# RH055_1.net
KiCad netlist of a schematic drawn in EAGLE
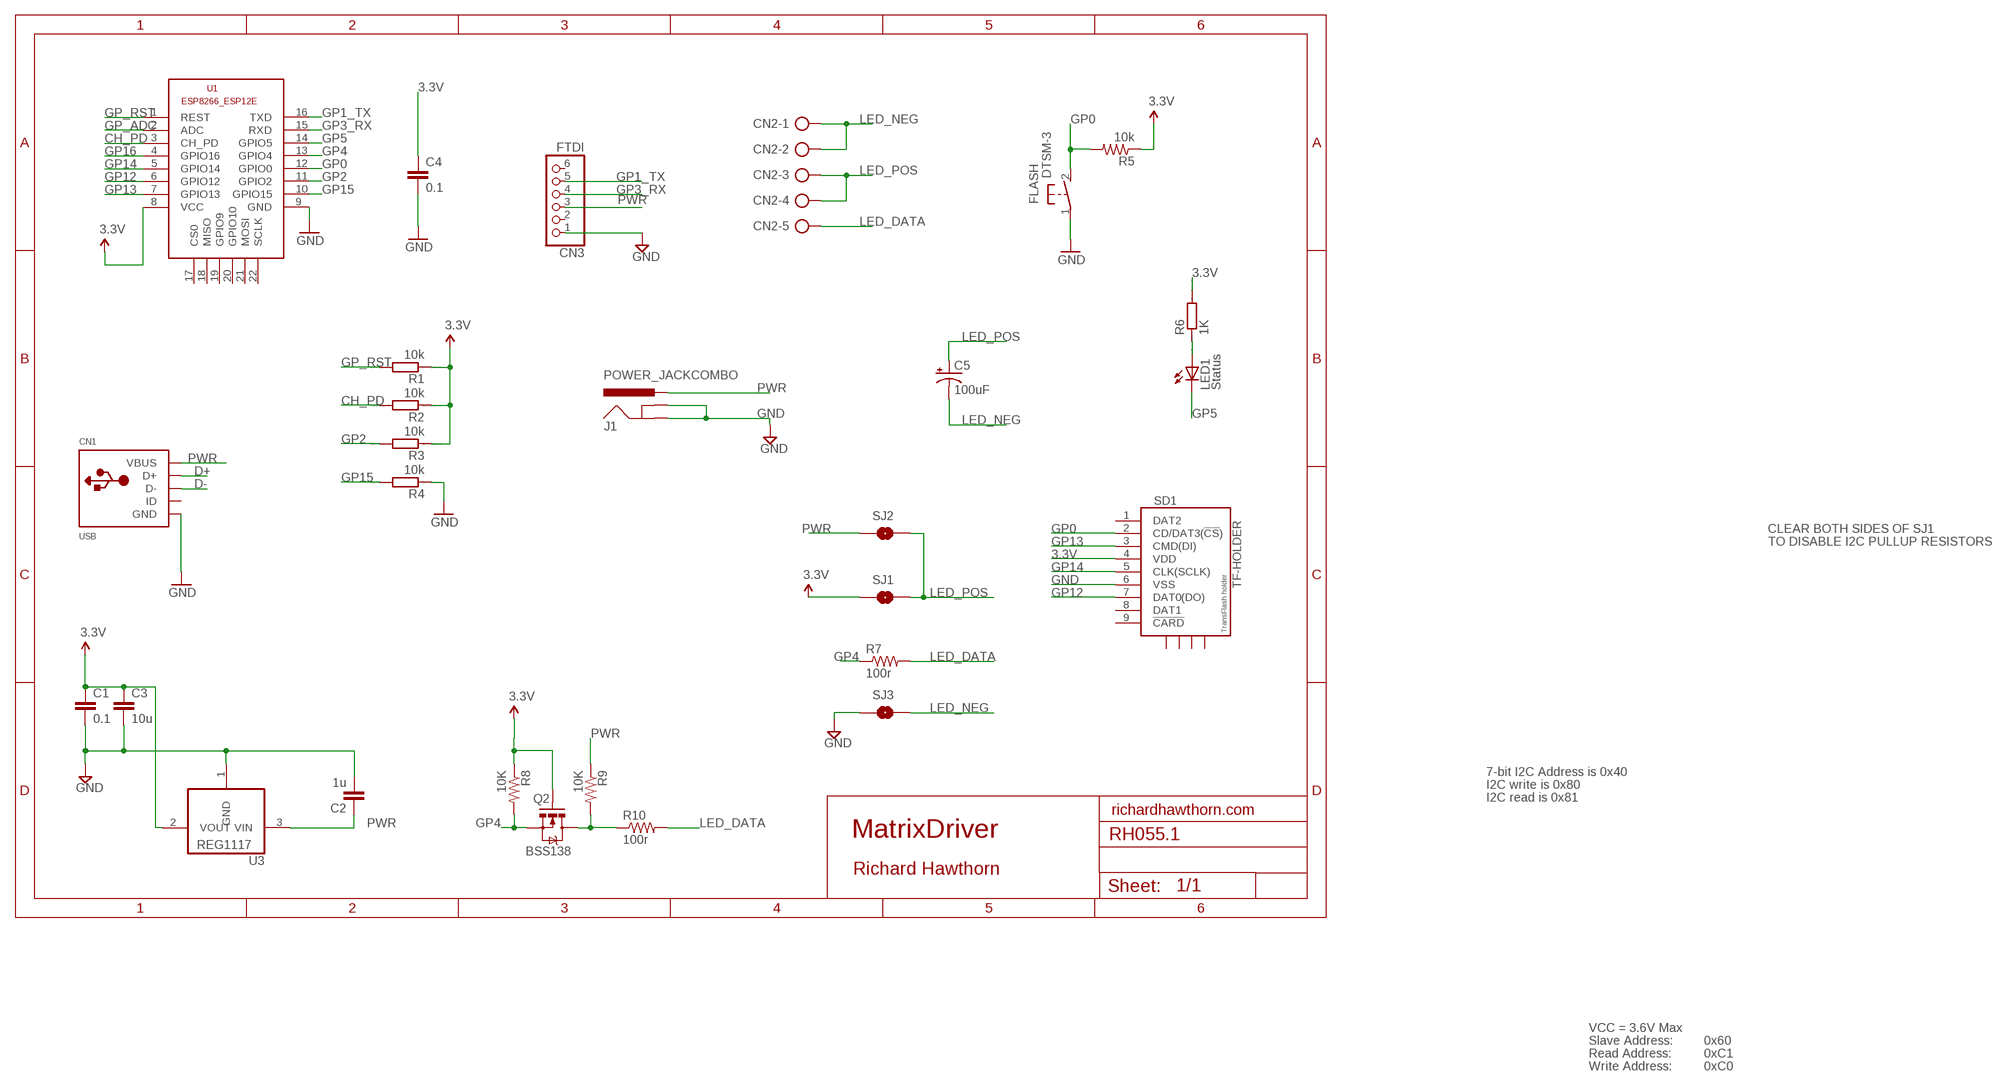
[diagram p0: schematic, sheet 1]

(export (version "E")
  (design (tool "Eeschema 10.0.6"))
  (components
    (comp (ref "C1")
      (value "0.1")
      (footprint "eagle-import:0603-CAP")
      (libsource (lib "eagle-import") (part "CAP0603-CAP"))
    )
    (comp (ref "C2")
      (value "1u")
      (footprint "eagle-import:0603-CAP")
      (libsource (lib "eagle-import") (part "CAP0603-CAP"))
    )
    (comp (ref "C3")
      (value "10u")
      (footprint "eagle-import:0805-CAP")
      (libsource (lib "eagle-import") (part "CAP0805-CAP"))
    )
    (comp (ref "C4")
      (value "0.1")
      (footprint "eagle-import:0603-CAP")
      (libsource (lib "eagle-import") (part "CAP0603-CAP"))
    )
    (comp (ref "C5")
      (value "100uF")
      (footprint "eagle-import:EIA7343")
      (libsource (lib "eagle-import") (part "100UF-10V-10%(TANT)"))
    )
    (comp (ref "CN1")
      (value "USB")
      (footprint "eagle-import:USB-MINIB")
      (libsource (lib "eagle-import") (part "USBMINIB"))
    )
    (comp (ref "CN2")
      (value "AK500/5")
      (footprint "eagle-import:AK500_5")
      (libsource (lib "eagle-import") (part "AK500/5"))
    )
    (comp (ref "CN3")
      (value "FTDI")
      (footprint "eagle-import:1X06")
      (libsource (lib "eagle-import") (part "PINHD-1X6"))
    )
    (comp (ref "FLASH")
      (value "DTSM-3")
      (footprint "eagle-import:DTSM-3")
      (libsource (lib "eagle-import") (part "DTSM-3"))
    )
    (comp (ref "J1")
      (value "POWER_JACKCOMBO")
      (footprint "eagle-import:POWER_JACK_COMBO")
      (libsource (lib "eagle-import") (part "POWER_JACKCOMBO"))
    )
    (comp (ref "LED1")
      (value "Status")
      (footprint "eagle-import:CHIPLED_0805")
      (libsource (lib "eagle-import") (part "LEDCHIPLED_0805"))
    )
    (comp (ref "Q2")
      (value "BSS138")
      (footprint "eagle-import:SOT23-3")
      (libsource (lib "eagle-import") (part "MOSFET-NCHANNELSMD"))
    )
    (comp (ref "R1")
      (value "10k")
      (footprint "eagle-import:R0603")
      (libsource (lib "eagle-import") (part "R-EU_R0603"))
    )
    (comp (ref "R2")
      (value "10k")
      (footprint "eagle-import:R0603")
      (libsource (lib "eagle-import") (part "R-EU_R0603"))
    )
    (comp (ref "R3")
      (value "10k")
      (footprint "eagle-import:R0603")
      (libsource (lib "eagle-import") (part "R-EU_R0603"))
    )
    (comp (ref "R4")
      (value "10k")
      (footprint "eagle-import:R0603")
      (libsource (lib "eagle-import") (part "R-EU_R0603"))
    )
    (comp (ref "R5")
      (value "10k")
      (footprint "eagle-import:0805")
      (libsource (lib "eagle-import") (part "SparkFun_RESISTOR0805-RES"))
    )
    (comp (ref "R6")
      (value "1K")
      (footprint "eagle-import:R0603")
      (libsource (lib "eagle-import") (part "R-EU_R0603"))
    )
    (comp (ref "R7")
      (value "100r")
      (footprint "eagle-import:0603-RES")
      (libsource (lib "eagle-import") (part "RESISTOR0603-RES"))
    )
    (comp (ref "R8")
      (value "10K")
      (footprint "eagle-import:0805")
      (libsource (lib "eagle-import") (part "SparkFun-Passives_RESISTOR0805-RES"))
    )
    (comp (ref "R9")
      (value "10K")
      (footprint "eagle-import:0805")
      (libsource (lib "eagle-import") (part "SparkFun-Passives_RESISTOR0805-RES"))
    )
    (comp (ref "R10")
      (value "100r")
      (footprint "eagle-import:0603-RES")
      (libsource (lib "eagle-import") (part "RESISTOR0603-RES"))
    )
    (comp (ref "SD1")
      (value "TF-HOLDER")
      (footprint "eagle-import:TF-PULL")
      (libsource (lib "eagle-import") (part "TF-HOLDER"))
    )
    (comp (ref "SJ1")
      (value "SOLDERJUMPERNO")
      (footprint "eagle-import:SJ_2S-NO")
      (libsource (lib "eagle-import") (part "SOLDERJUMPERNO"))
    )
    (comp (ref "SJ2")
      (value "SOLDERJUMPERNO")
      (footprint "eagle-import:SJ_2S-NO")
      (libsource (lib "eagle-import") (part "SOLDERJUMPERNO"))
    )
    (comp (ref "SJ3")
      (value "SOLDERJUMPERNO")
      (footprint "eagle-import:SJ_2S-NO")
      (libsource (lib "eagle-import") (part "SOLDERJUMPERNO"))
    )
    (comp (ref "U1")
      (value "ESP8266-12EESP8266-ESP12E")
      (footprint "eagle-import:ESP8266-ESP12E")
      (libsource (lib "eagle-import") (part "ESP8266-12EESP8266-ESP12E"))
    )
    (comp (ref "U3")
      (value "REG1117")
      (footprint "eagle-import:SOT223")
      (libsource (lib "eagle-import") (part "REG1117"))
    )
  )
  (nets
    (net (code "1") (name "/CH_PD") (class "Default")
      (node (ref "R2") (pin "2") (pinfunction "2_2") (pintype "passive"))
      (node (ref "U1") (pin "3") (pinfunction "CH_PD_3") (pintype "bidirectional"))
    )
    (net (code "2") (name "/D+") (class "Default")
      (node (ref "CN1") (pin "D+") (pinfunction "D+_D+") (pintype "bidirectional"))
    )
    (net (code "3") (name "/D-") (class "Default")
      (node (ref "CN1") (pin "D-") (pinfunction "D-_D-") (pintype "bidirectional"))
    )
    (net (code "4") (name "/GP0") (class "Default")
      (node (ref "FLASH") (pin "2") (pinfunction "2_2") (pintype "passive"))
      (node (ref "R5") (pin "2") (pinfunction "2_2") (pintype "passive"))
      (node (ref "SD1") (pin "2") (pinfunction "CD/DAT3(~{CS})_2") (pintype "bidirectional"))
      (node (ref "U1") (pin "12") (pinfunction "GPIO0_12") (pintype "bidirectional"))
    )
    (net (code "5") (name "/GP1_TX") (class "Default")
      (node (ref "CN3") (pin "5") (pinfunction "5_5") (pintype "passive"))
      (node (ref "U1") (pin "16") (pinfunction "TXD_16") (pintype "bidirectional"))
    )
    (net (code "6") (name "/GP2") (class "Default")
      (node (ref "R3") (pin "2") (pinfunction "2_2") (pintype "passive"))
      (node (ref "U1") (pin "11") (pinfunction "GPIO2_11") (pintype "bidirectional"))
    )
    (net (code "7") (name "/GP3_RX") (class "Default")
      (node (ref "CN3") (pin "4") (pinfunction "4_4") (pintype "passive"))
      (node (ref "U1") (pin "15") (pinfunction "RXD_15") (pintype "bidirectional"))
    )
    (net (code "8") (name "/GP4") (class "Default")
      (node (ref "Q2") (pin "2") (pinfunction "S_2") (pintype "passive"))
      (node (ref "R7") (pin "1") (pinfunction "1_1") (pintype "passive"))
      (node (ref "R8") (pin "2") (pinfunction "2_2") (pintype "passive"))
      (node (ref "U1") (pin "13") (pinfunction "GPIO4_13") (pintype "bidirectional"))
    )
    (net (code "9") (name "/GP5") (class "Default")
      (node (ref "LED1") (pin "C") (pinfunction "C_C") (pintype "passive"))
      (node (ref "U1") (pin "14") (pinfunction "GPIO5_14") (pintype "bidirectional"))
    )
    (net (code "10") (name "/GP12") (class "Default")
      (node (ref "SD1") (pin "7") (pinfunction "DAT0(DO)_7") (pintype "bidirectional"))
      (node (ref "U1") (pin "6") (pinfunction "GPIO12_6") (pintype "bidirectional"))
    )
    (net (code "11") (name "/GP13") (class "Default")
      (node (ref "SD1") (pin "3") (pinfunction "CMD(DI)_3") (pintype "bidirectional"))
      (node (ref "U1") (pin "7") (pinfunction "GPIO13_7") (pintype "bidirectional"))
    )
    (net (code "12") (name "/GP14") (class "Default")
      (node (ref "SD1") (pin "5") (pinfunction "CLK(SCLK)_5") (pintype "input"))
      (node (ref "U1") (pin "5") (pinfunction "GPIO14_5") (pintype "bidirectional"))
    )
    (net (code "13") (name "/GP15") (class "Default")
      (node (ref "R4") (pin "2") (pinfunction "2_2") (pintype "passive"))
      (node (ref "U1") (pin "10") (pinfunction "GPIO15_10") (pintype "bidirectional"))
    )
    (net (code "14") (name "/GP16") (class "Default")
      (node (ref "U1") (pin "4") (pinfunction "GPIO16_4") (pintype "bidirectional"))
    )
    (net (code "15") (name "/GP_ADC") (class "Default")
      (node (ref "U1") (pin "2") (pinfunction "ADC_2") (pintype "bidirectional"))
    )
    (net (code "16") (name "/GP_RST") (class "Default")
      (node (ref "R1") (pin "2") (pinfunction "2_2") (pintype "passive"))
      (node (ref "U1") (pin "1") (pinfunction "REST_1") (pintype "bidirectional"))
    )
    (net (code "17") (name "/LED_DATA") (class "Default")
      (node (ref "CN2") (pin "5") (pinfunction "KL_5") (pintype "passive"))
      (node (ref "R10") (pin "2") (pinfunction "2_2") (pintype "passive"))
      (node (ref "R7") (pin "2") (pinfunction "2_2") (pintype "passive"))
    )
    (net (code "18") (name "/LED_NEG") (class "Default")
      (node (ref "C5") (pin "C") (pinfunction "-_C") (pintype "passive"))
      (node (ref "CN2") (pin "1") (pinfunction "KL_1") (pintype "passive"))
      (node (ref "CN2") (pin "2") (pinfunction "KL_2") (pintype "passive"))
      (node (ref "SJ3") (pin "2") (pinfunction "2_2") (pintype "passive"))
    )
    (net (code "19") (name "/LED_POS") (class "Default")
      (node (ref "C5") (pin "A") (pinfunction "+_A") (pintype "passive"))
      (node (ref "CN2") (pin "3") (pinfunction "KL_3") (pintype "passive"))
      (node (ref "CN2") (pin "4") (pinfunction "KL_4") (pintype "passive"))
      (node (ref "SJ1") (pin "2") (pinfunction "2_2") (pintype "passive"))
      (node (ref "SJ2") (pin "2") (pinfunction "2_2") (pintype "passive"))
    )
    (net (code "20") (name "/PWR") (class "Default")
      (node (ref "C2") (pin "1") (pinfunction "1_1") (pintype "passive"))
      (node (ref "CN1") (pin "VBUS") (pinfunction "VBUS_VBUS") (pintype "power_in"))
      (node (ref "CN3") (pin "3") (pinfunction "3_3") (pintype "passive"))
      (node (ref "J1") (pin "POWER") (pinfunction "PWR_POWER") (pintype "bidirectional"))
      (node (ref "R9") (pin "1") (pinfunction "1_1") (pintype "passive"))
      (node (ref "SJ2") (pin "1") (pinfunction "1_1") (pintype "passive"))
      (node (ref "U3") (pin "3") (pinfunction "VIN_3") (pintype "input"))
    )
    (net (code "21") (name "3.3V") (class "Default")
      (node (ref "C1") (pin "1") (pinfunction "1_1") (pintype "passive"))
      (node (ref "C3") (pin "1") (pinfunction "1_1") (pintype "passive"))
      (node (ref "C4") (pin "1") (pinfunction "1_1") (pintype "passive"))
      (node (ref "Q2") (pin "1") (pinfunction "G_1") (pintype "passive"))
      (node (ref "R1") (pin "1") (pinfunction "1_1") (pintype "passive"))
      (node (ref "R2") (pin "1") (pinfunction "1_1") (pintype "passive"))
      (node (ref "R3") (pin "1") (pinfunction "1_1") (pintype "passive"))
      (node (ref "R5") (pin "1") (pinfunction "1_1") (pintype "passive"))
      (node (ref "R6") (pin "2") (pinfunction "2_2") (pintype "passive"))
      (node (ref "R8") (pin "1") (pinfunction "1_1") (pintype "passive"))
      (node (ref "SD1") (pin "4") (pinfunction "VDD_4") (pintype "power_in"))
      (node (ref "SJ1") (pin "1") (pinfunction "1_1") (pintype "passive"))
      (node (ref "U1") (pin "8") (pinfunction "VCC_8") (pintype "bidirectional"))
      (node (ref "U3") (pin "2") (pinfunction "VOUT_2") (pintype "output"))
    )
    (net (code "22") (name "GND") (class "Default")
      (node (ref "C1") (pin "2") (pinfunction "2_2") (pintype "passive"))
      (node (ref "C2") (pin "2") (pinfunction "2_2") (pintype "passive"))
      (node (ref "C3") (pin "2") (pinfunction "2_2") (pintype "passive"))
      (node (ref "C4") (pin "2") (pinfunction "2_2") (pintype "passive"))
      (node (ref "CN1") (pin "GND") (pinfunction "GND_GND") (pintype "power_in"))
      (node (ref "CN3") (pin "1") (pinfunction "1_1") (pintype "passive"))
      (node (ref "FLASH") (pin "1") (pinfunction "1_1") (pintype "passive"))
      (node (ref "J1") (pin "GND") (pinfunction "GNDBREAK_GND") (pintype "bidirectional"))
      (node (ref "J1") (pin "GND@1") (pinfunction "GND_GND@1") (pintype "bidirectional"))
      (node (ref "R4") (pin "1") (pinfunction "1_1") (pintype "passive"))
      (node (ref "SD1") (pin "6") (pinfunction "VSS_6") (pintype "power_in"))
      (node (ref "SJ3") (pin "1") (pinfunction "1_1") (pintype "passive"))
      (node (ref "U1") (pin "9") (pinfunction "GND_9") (pintype "bidirectional"))
      (node (ref "U3") (pin "1") (pinfunction "GND_1") (pintype "power_in"))
    )
    (net (code "23") (name "Net-(LED1-PadA)") (class "Default")
      (node (ref "LED1") (pin "A") (pinfunction "A_A") (pintype "passive"))
      (node (ref "R6") (pin "1") (pinfunction "1_1") (pintype "passive"))
    )
    (net (code "24") (name "Net-(Q2-D)") (class "Default")
      (node (ref "Q2") (pin "3") (pinfunction "D_3") (pintype "passive"))
      (node (ref "R10") (pin "1") (pinfunction "1_1") (pintype "passive"))
      (node (ref "R9") (pin "2") (pinfunction "2_2") (pintype "passive"))
    )
    (net (code "25") (name "unconnected-(CN1-PadID)") (class "Default")
      (node (ref "CN1") (pin "ID") (pinfunction "ID_ID") (pintype "bidirectional"))
    )
    (net (code "26") (name "unconnected-(CN3-Pad2)") (class "Default")
      (node (ref "CN3") (pin "2") (pinfunction "2_2") (pintype "passive"))
    )
    (net (code "27") (name "unconnected-(CN3-Pad6)") (class "Default")
      (node (ref "CN3") (pin "6") (pinfunction "6_6") (pintype "passive"))
    )
    (net (code "28") (name "unconnected-(SD1-DAT1-Pad8)") (class "Default")
      (node (ref "SD1") (pin "8") (pinfunction "DAT1_8") (pintype "bidirectional"))
    )
    (net (code "29") (name "unconnected-(SD1-DAT2-Pad1)") (class "Default")
      (node (ref "SD1") (pin "1") (pinfunction "DAT2_1") (pintype "bidirectional"))
    )
    (net (code "30") (name "unconnected-(SD1-PadS1)") (class "Default")
      (node (ref "SD1") (pin "S1") (pinfunction "S1_S1") (pintype "passive"))
    )
    (net (code "31") (name "unconnected-(SD1-PadS2)") (class "Default")
      (node (ref "SD1") (pin "S2") (pinfunction "S2_S2") (pintype "passive"))
    )
    (net (code "32") (name "unconnected-(SD1-PadS3)") (class "Default")
      (node (ref "SD1") (pin "S3") (pinfunction "S3_S3") (pintype "passive"))
    )
    (net (code "33") (name "unconnected-(SD1-PadS4)") (class "Default")
      (node (ref "SD1") (pin "S4") (pinfunction "S4_S4") (pintype "passive"))
    )
    (net (code "34") (name "unconnected-(SD1-~{CARD}-Pad9)") (class "Default")
      (node (ref "SD1") (pin "9") (pinfunction "~{CARD}_9") (pintype "passive"))
    )
    (net (code "35") (name "unconnected-(U1-CS0-Pad17)") (class "Default")
      (node (ref "U1") (pin "17") (pinfunction "CS0_17") (pintype "bidirectional"))
    )
    (net (code "36") (name "unconnected-(U1-GPIO9-Pad19)") (class "Default")
      (node (ref "U1") (pin "19") (pinfunction "GPIO9_19") (pintype "bidirectional"))
    )
    (net (code "37") (name "unconnected-(U1-GPIO10-Pad20)") (class "Default")
      (node (ref "U1") (pin "20") (pinfunction "GPIO10_20") (pintype "bidirectional"))
    )
    (net (code "38") (name "unconnected-(U1-MISO-Pad18)") (class "Default")
      (node (ref "U1") (pin "18") (pinfunction "MISO_18") (pintype "bidirectional"))
    )
    (net (code "39") (name "unconnected-(U1-MOSI-Pad21)") (class "Default")
      (node (ref "U1") (pin "21") (pinfunction "MOSI_21") (pintype "bidirectional"))
    )
    (net (code "40") (name "unconnected-(U1-SCLK-Pad22)") (class "Default")
      (node (ref "U1") (pin "22") (pinfunction "SCLK_22") (pintype "bidirectional"))
    )
  )
)
